# working.net
KiCad netlist of a schematic drawn in EAGLE
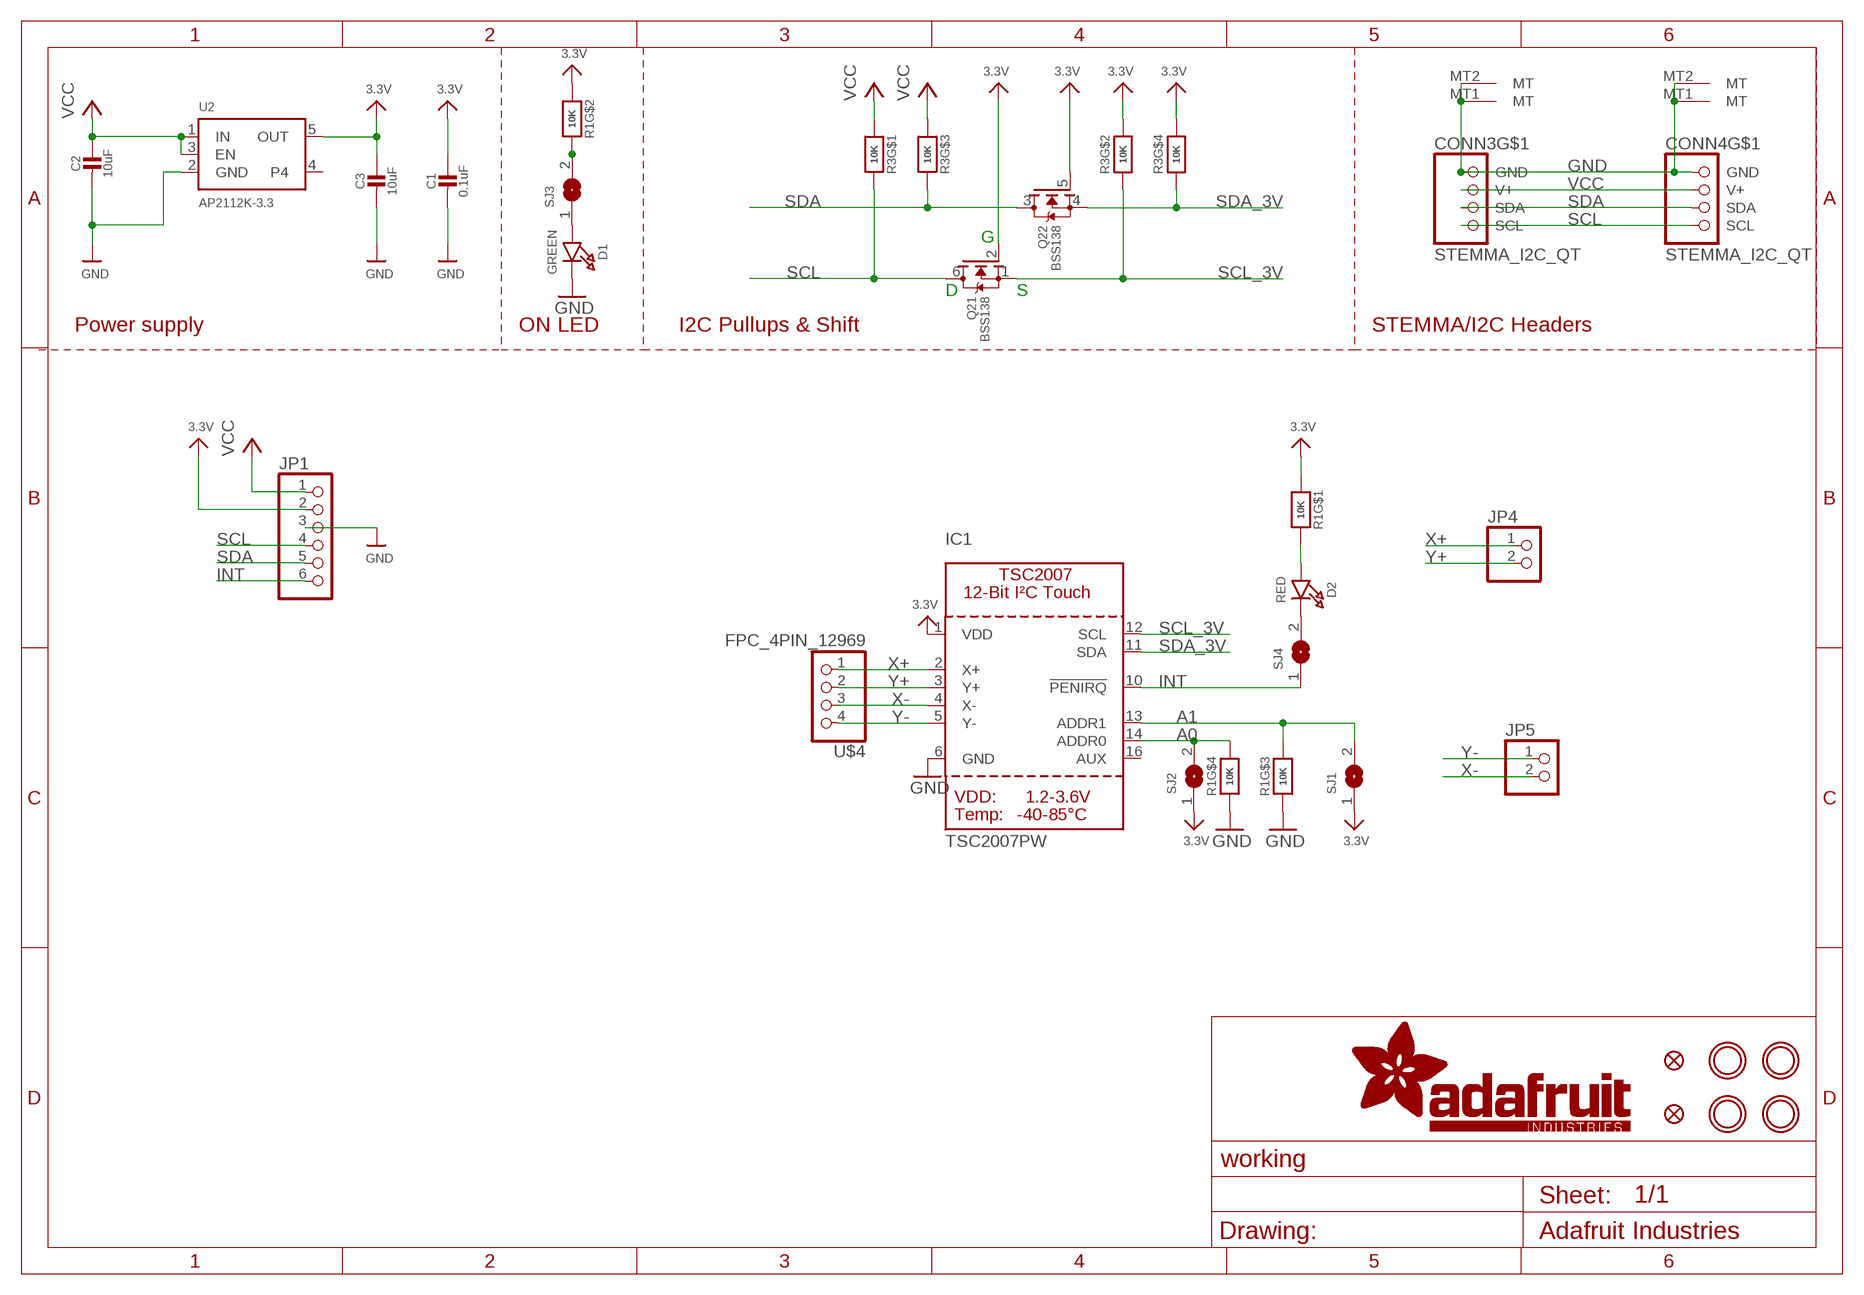
[diagram p0: schematic, sheet 1]

(export (version "E")
  (design (tool "Eeschema 10.0.6"))
  (components
    (comp (ref "C1")
      (value "0.1uF")
      (footprint "eagle-import:0603-NO")
      (libsource (lib "eagle-import") (part "CAP_CERAMIC0603_NO"))
    )
    (comp (ref "C2")
      (value "10uF")
      (footprint "eagle-import:0805-NO")
      (libsource (lib "eagle-import") (part "CAP_CERAMIC0805-NOOUTLINE"))
    )
    (comp (ref "C3")
      (value "10uF")
      (footprint "eagle-import:0805-NO")
      (libsource (lib "eagle-import") (part "CAP_CERAMIC0805-NOOUTLINE"))
    )
    (comp (ref "CONN3")
      (value "STEMMA_I2C_QT")
      (footprint "eagle-import:JST_SH4")
      (libsource (lib "eagle-import") (part "STEMMA_I2C_QT"))
    )
    (comp (ref "CONN4")
      (value "STEMMA_I2C_QT")
      (footprint "eagle-import:JST_SH4")
      (libsource (lib "eagle-import") (part "STEMMA_I2C_QT"))
    )
    (comp (ref "D1")
      (value "GREEN")
      (footprint "eagle-import:CHIPLED_0603_NOOUTLINE")
      (libsource (lib "eagle-import") (part "LED0603_NOOUTLINE"))
    )
    (comp (ref "D2")
      (value "RED")
      (footprint "eagle-import:CHIPLED_0603_NOOUTLINE")
      (libsource (lib "eagle-import") (part "LED0603_NOOUTLINE"))
    )
    (comp (ref "FID3")
      (value "FIDUCIAL_1MM")
      (footprint "eagle-import:FIDUCIAL_1MM")
      (libsource (lib "eagle-import") (part "FIDUCIAL_1MM"))
    )
    (comp (ref "FID4")
      (value "FIDUCIAL_1MM")
      (footprint "eagle-import:FIDUCIAL_1MM")
      (libsource (lib "eagle-import") (part "FIDUCIAL_1MM"))
    )
    (comp (ref "IC1")
      (value "TSC2007PW")
      (footprint "eagle-import:TSSOP16")
      (libsource (lib "eagle-import") (part "TSC2007PW"))
    )
    (comp (ref "JP1")
      (value "HEADER-1X670MIL")
      (footprint "eagle-import:1X06_ROUND_70")
      (libsource (lib "eagle-import") (part "HEADER-1X670MIL"))
    )
    (comp (ref "JP4")
      (value "HEADER-1X2ROUND")
      (footprint "eagle-import:1X02_ROUND")
      (libsource (lib "eagle-import") (part "HEADER-1X2ROUND"))
    )
    (comp (ref "JP5")
      (value "HEADER-1X2ROUND")
      (footprint "eagle-import:1X02_ROUND")
      (libsource (lib "eagle-import") (part "HEADER-1X2ROUND"))
    )
    (comp (ref "Q2")
      (value "BSS138")
      (footprint "eagle-import:SOT363")
      (libsource (lib "eagle-import") (part "MOSFET-N_DUAL"))
    )
    (comp (ref "R1")
      (value "10K")
      (footprint "eagle-import:RESPACK_4X0603")
      (libsource (lib "eagle-import") (part "RESISTOR_4PACK"))
    )
    (comp (ref "R3")
      (value "10K")
      (footprint "eagle-import:RESPACK_4X0603")
      (libsource (lib "eagle-import") (part "RESISTOR_4PACK"))
    )
    (comp (ref "SJ1")
      (value "SOLDERJUMPER")
      (footprint "eagle-import:SOLDERJUMPER_ARROW_NOPASTE")
      (libsource (lib "eagle-import") (part "SOLDERJUMPER"))
    )
    (comp (ref "SJ2")
      (value "SOLDERJUMPER")
      (footprint "eagle-import:SOLDERJUMPER_ARROW_NOPASTE")
      (libsource (lib "eagle-import") (part "SOLDERJUMPER"))
    )
    (comp (ref "SJ3")
      (value "SOLDERJUMPERCLOSED")
      (footprint "eagle-import:SOLDERJUMPER_CLOSEDWIRE")
      (libsource (lib "eagle-import") (part "SOLDERJUMPERCLOSED"))
    )
    (comp (ref "SJ4")
      (value "SOLDERJUMPERCLOSED")
      (footprint "eagle-import:SOLDERJUMPER_CLOSEDWIRE")
      (libsource (lib "eagle-import") (part "SOLDERJUMPERCLOSED"))
    )
    (comp (ref "U$1")
      (value "MOUNTINGHOLE2.5")
      (footprint "eagle-import:MOUNTINGHOLE_2.5_PLATED")
      (libsource (lib "eagle-import") (part "MOUNTINGHOLE2.5"))
    )
    (comp (ref "U$4")
      (value "FPC_4PIN_12969")
      (footprint "eagle-import:FPC_CONN_1MM_DUAL_4P")
      (libsource (lib "eagle-import") (part "FPC_4PIN_12969"))
    )
    (comp (ref "U$17")
      (value "MOUNTINGHOLE2.5")
      (footprint "eagle-import:MOUNTINGHOLE_2.5_PLATED")
      (libsource (lib "eagle-import") (part "MOUNTINGHOLE2.5"))
    )
    (comp (ref "U$19")
      (value "MOUNTINGHOLE2.5")
      (footprint "eagle-import:MOUNTINGHOLE_2.5_PLATED")
      (libsource (lib "eagle-import") (part "MOUNTINGHOLE2.5"))
    )
    (comp (ref "U$21")
      (value "MOUNTINGHOLE2.5")
      (footprint "eagle-import:MOUNTINGHOLE_2.5_PLATED")
      (libsource (lib "eagle-import") (part "MOUNTINGHOLE2.5"))
    )
    (comp (ref "U2")
      (value "AP2112K-3.3")
      (footprint "eagle-import:SOT23-5")
      (libsource (lib "eagle-import") (part "VREG_SOT23-5"))
    )
  )
  (nets
    (net (code "1") (name "/A0") (class "Default")
      (node (ref "IC1") (pin "14") (pinfunction "ADDR0_14") (pintype "input"))
      (node (ref "R1") (pin "5") (pinfunction "2_5") (pintype "passive"))
      (node (ref "SJ2") (pin "2") (pinfunction "2_2") (pintype "passive"))
    )
    (net (code "2") (name "/A1") (class "Default")
      (node (ref "IC1") (pin "13") (pinfunction "ADDR1_13") (pintype "input"))
      (node (ref "R1") (pin "6") (pinfunction "2_6") (pintype "passive"))
      (node (ref "SJ1") (pin "2") (pinfunction "2_2") (pintype "passive"))
    )
    (net (code "3") (name "/INT") (class "Default")
      (node (ref "IC1") (pin "10") (pinfunction "~{PENIRQ}_10") (pintype "output"))
      (node (ref "JP1") (pin "6") (pinfunction "6_6") (pintype "passive"))
      (node (ref "SJ4") (pin "1") (pinfunction "1_1") (pintype "passive"))
    )
    (net (code "4") (name "/SCL") (class "Default")
      (node (ref "CONN3") (pin "4") (pinfunction "SCL_4") (pintype "passive"))
      (node (ref "CONN4") (pin "4") (pinfunction "SCL_4") (pintype "passive"))
      (node (ref "JP1") (pin "4") (pinfunction "4_4") (pintype "passive"))
      (node (ref "Q2") (pin "6") (pinfunction "D_6") (pintype "bidirectional"))
      (node (ref "R3") (pin "8") (pinfunction "2_8") (pintype "passive"))
    )
    (net (code "5") (name "/SCL_3V") (class "Default")
      (node (ref "IC1") (pin "12") (pinfunction "SCL_12") (pintype "bidirectional"))
      (node (ref "Q2") (pin "1") (pinfunction "S_1") (pintype "bidirectional"))
      (node (ref "R3") (pin "7") (pinfunction "2_7") (pintype "passive"))
    )
    (net (code "6") (name "/SDA") (class "Default")
      (node (ref "CONN3") (pin "3") (pinfunction "SDA_3") (pintype "passive"))
      (node (ref "CONN4") (pin "3") (pinfunction "SDA_3") (pintype "passive"))
      (node (ref "JP1") (pin "5") (pinfunction "5_5") (pintype "passive"))
      (node (ref "Q2") (pin "3") (pinfunction "D_3") (pintype "bidirectional"))
      (node (ref "R3") (pin "6") (pinfunction "2_6") (pintype "passive"))
    )
    (net (code "7") (name "/SDA_3V") (class "Default")
      (node (ref "IC1") (pin "11") (pinfunction "SDA_11") (pintype "bidirectional"))
      (node (ref "Q2") (pin "4") (pinfunction "S_4") (pintype "bidirectional"))
      (node (ref "R3") (pin "5") (pinfunction "2_5") (pintype "passive"))
    )
    (net (code "8") (name "/X+") (class "Default")
      (node (ref "IC1") (pin "2") (pinfunction "X+_2") (pintype "input"))
      (node (ref "JP4") (pin "1") (pinfunction "1_1") (pintype "passive"))
      (node (ref "U$4") (pin "1") (pinfunction "4_1") (pintype "passive"))
    )
    (net (code "9") (name "/X-") (class "Default")
      (node (ref "IC1") (pin "4") (pinfunction "X-_4") (pintype "input"))
      (node (ref "JP5") (pin "2") (pinfunction "2_2") (pintype "passive"))
      (node (ref "U$4") (pin "3") (pinfunction "2_3") (pintype "passive"))
    )
    (net (code "10") (name "/Y+") (class "Default")
      (node (ref "IC1") (pin "3") (pinfunction "Y+_3") (pintype "input"))
      (node (ref "JP4") (pin "2") (pinfunction "2_2") (pintype "passive"))
      (node (ref "U$4") (pin "2") (pinfunction "3_2") (pintype "passive"))
    )
    (net (code "11") (name "/Y-") (class "Default")
      (node (ref "IC1") (pin "5") (pinfunction "Y-_5") (pintype "input"))
      (node (ref "JP5") (pin "1") (pinfunction "1_1") (pintype "passive"))
      (node (ref "U$4") (pin "4") (pinfunction "1_4") (pintype "passive"))
    )
    (net (code "12") (name "3.3V") (class "Default")
      (node (ref "C1") (pin "1") (pinfunction "1_1") (pintype "passive"))
      (node (ref "C3") (pin "1") (pinfunction "1_1") (pintype "passive"))
      (node (ref "IC1") (pin "1") (pinfunction "VDD_1") (pintype "bidirectional"))
      (node (ref "JP1") (pin "2") (pinfunction "2_2") (pintype "passive"))
      (node (ref "Q2") (pin "2") (pinfunction "G_2") (pintype "bidirectional"))
      (node (ref "Q2") (pin "5") (pinfunction "G_5") (pintype "bidirectional"))
      (node (ref "R1") (pin "1") (pinfunction "1_1") (pintype "passive"))
      (node (ref "R1") (pin "2") (pinfunction "1_2") (pintype "passive"))
      (node (ref "R3") (pin "2") (pinfunction "1_2") (pintype "passive"))
      (node (ref "R3") (pin "4") (pinfunction "1_4") (pintype "passive"))
      (node (ref "SJ1") (pin "1") (pinfunction "1_1") (pintype "passive"))
      (node (ref "SJ2") (pin "1") (pinfunction "1_1") (pintype "passive"))
      (node (ref "U2") (pin "5") (pinfunction "OUT_5") (pintype "power_in"))
    )
    (net (code "13") (name "GND") (class "Default")
      (node (ref "C1") (pin "2") (pinfunction "2_2") (pintype "passive"))
      (node (ref "C2") (pin "2") (pinfunction "2_2") (pintype "passive"))
      (node (ref "C3") (pin "2") (pinfunction "2_2") (pintype "passive"))
      (node (ref "CONN3") (pin "1") (pinfunction "GND_1") (pintype "passive"))
      (node (ref "CONN3") (pin "MT1") (pinfunction "MT_MT1") (pintype "bidirectional"))
      (node (ref "CONN3") (pin "MT2") (pinfunction "MT_MT2") (pintype "bidirectional"))
      (node (ref "CONN4") (pin "1") (pinfunction "GND_1") (pintype "passive"))
      (node (ref "CONN4") (pin "MT1") (pinfunction "MT_MT1") (pintype "bidirectional"))
      (node (ref "CONN4") (pin "MT2") (pinfunction "MT_MT2") (pintype "bidirectional"))
      (node (ref "D1") (pin "C") (pinfunction "C_C") (pintype "passive"))
      (node (ref "IC1") (pin "6") (pinfunction "GND_6") (pintype "bidirectional"))
      (node (ref "JP1") (pin "3") (pinfunction "3_3") (pintype "passive"))
      (node (ref "R1") (pin "3") (pinfunction "1_3") (pintype "passive"))
      (node (ref "R1") (pin "4") (pinfunction "1_4") (pintype "passive"))
      (node (ref "U2") (pin "2") (pinfunction "GND_2") (pintype "power_in"))
    )
    (net (code "14") (name "Net-(D1-PadA)") (class "Default")
      (node (ref "D1") (pin "A") (pinfunction "A_A") (pintype "passive"))
      (node (ref "SJ3") (pin "1") (pinfunction "1_1") (pintype "passive"))
    )
    (net (code "15") (name "Net-(D2-PadC)") (class "Default")
      (node (ref "D2") (pin "C") (pinfunction "C_C") (pintype "passive"))
      (node (ref "SJ4") (pin "2") (pinfunction "2_2") (pintype "passive"))
    )
    (net (code "16") (name "Net-(R1A-2)") (class "Default")
      (node (ref "D2") (pin "A") (pinfunction "A_A") (pintype "passive"))
      (node (ref "R1") (pin "8") (pinfunction "2_8") (pintype "passive"))
    )
    (net (code "17") (name "Net-(R1B-2)") (class "Default")
      (node (ref "R1") (pin "7") (pinfunction "2_7") (pintype "passive"))
      (node (ref "SJ3") (pin "2") (pinfunction "2_2") (pintype "passive"))
    )
    (net (code "18") (name "VCC") (class "Default")
      (node (ref "C2") (pin "1") (pinfunction "1_1") (pintype "passive"))
      (node (ref "CONN3") (pin "2") (pinfunction "V+_2") (pintype "passive"))
      (node (ref "CONN4") (pin "2") (pinfunction "V+_2") (pintype "passive"))
      (node (ref "JP1") (pin "1") (pinfunction "1_1") (pintype "passive"))
      (node (ref "R3") (pin "1") (pinfunction "1_1") (pintype "passive"))
      (node (ref "R3") (pin "3") (pinfunction "1_3") (pintype "passive"))
      (node (ref "U2") (pin "1") (pinfunction "IN_1") (pintype "power_in"))
      (node (ref "U2") (pin "3") (pinfunction "EN_3") (pintype "input"))
    )
    (net (code "19") (name "unconnected-(IC1-AUX-Pad16)") (class "Default")
      (node (ref "IC1") (pin "16") (pinfunction "AUX_16") (pintype "input"))
    )
    (net (code "20") (name "unconnected-(U2-P4-Pad4)") (class "Default")
      (node (ref "U2") (pin "4") (pinfunction "P4_4") (pintype "bidirectional"))
    )
  )
)
